# MCH_FPGA_Power.net
KiCad netlist of a schematic drawn in Altium Designer
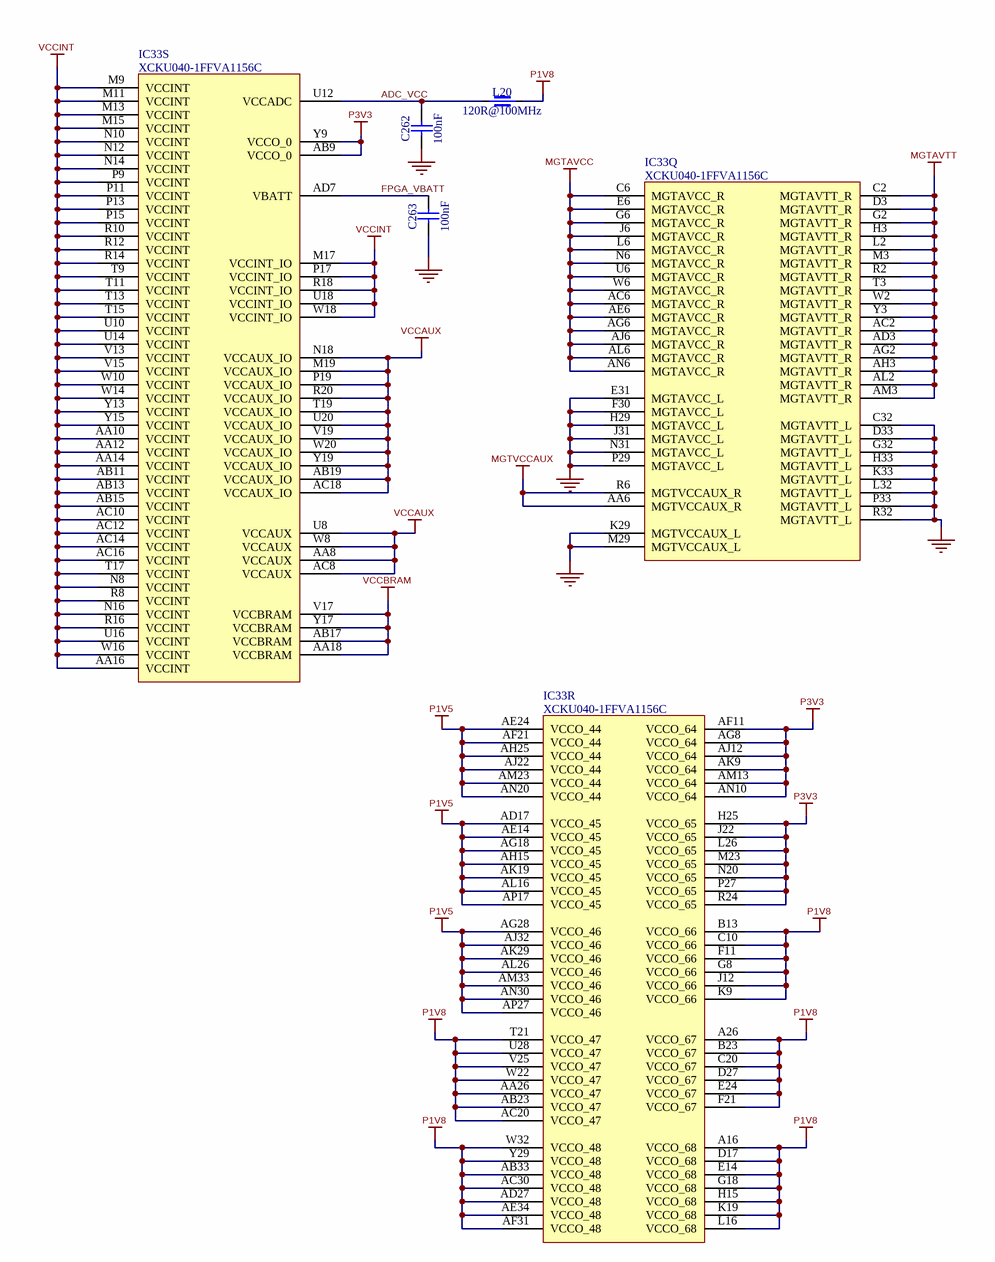
[diagram p0: MCH_FPGA_Power.SchDoc]

(export (version "E")
  (design (tool "Eeschema 10.0.6"))
  (components
    (comp (ref "C262")
      (value "100nF")
      (footprint "CAPC0603X33N")
      (description "Non-polarised capacitor")
      (fields
        (field (name "MANUFACTURER PART NUMBER") "CC0201_100NF_6.3V_10%_X5R")
        (field (name "MANUFACTURER") "GENERIC")
        (field (name "AUTHOR") "CERN DEM JLC")
      )
      (libsource (lib "Capacitors") (part "Capacitor - non polarized"))
    )
    (comp (ref "C263")
      (value "100nF")
      (footprint "CAPC0603X33N")
      (description "Non-polarised capacitor")
      (fields
        (field (name "MANUFACTURER PART NUMBER") "CC0201_100NF_6.3V_10%_X5R")
        (field (name "MANUFACTURER") "GENERIC")
        (field (name "AUTHOR") "CERN DEM JLC")
      )
      (libsource (lib "Capacitors") (part "Capacitor - non polarized"))
    )
    (comp (ref "IC33")
      (value "XCKU040-1FFVA1156C")
      (footprint "BGA1156C100P34X34_3500X3500X350")
      (description "Kintex UltraScale FPGA, 520 I/O, 530K Cells, 1156-Ball BGA, Speed Grade 1, Commercial Grade")
      (fields (field (name "MANUFACTURER") "XILINX") (field (name "AUTHOR") "CERN DEM CA"))
      (libsource (lib "ICs And Semiconductors") (part "XCKU040-1FFVA1156C"))
    )
    (comp (ref "L20")
      (value "120R@100MHz")
      (footprint "INDC1005X55N")
      (fields
        (field (name "MANUFACTURER PART NUMBER") "BLM15PX121SN1D")
        (field (name "MANUFACTURER") "MURATA")
        (field (name "PART NUMBER") "IND0402_MURATA_BLM15PX121SN1D")
        (field (name "AUTHOR") "CERN DEM JMW")
      )
      (libsource (lib "Inductors & Transformers") (part "Ferrite Bead"))
    )
  )
  (nets
    (net (code "1") (name "/ADC_VCC") (class "Default")
      (node (ref "C262") (pin "2") (pinfunction "2_2") (pintype "passive"))
      (node (ref "IC33") (pin "U12") (pinfunction "VCCADC_U12") (pintype "power_in"))
      (node (ref "L20") (pin "1") (pinfunction "1_1") (pintype "passive"))
    )
    (net (code "2") (name "/FPGA_VBATT") (class "Default")
      (node (ref "C263") (pin "2") (pinfunction "2_2") (pintype "passive"))
      (node (ref "IC33") (pin "AD7") (pinfunction "VBATT_AD7") (pintype "power_in"))
    )
    (net (code "3") (name "GND") (class "Default")
      (node (ref "C262") (pin "1") (pinfunction "1_1") (pintype "passive"))
      (node (ref "C263") (pin "1") (pinfunction "1_1") (pintype "passive"))
      (node (ref "IC33") (pin "C32") (pinfunction "MGTAVTT_L_C32") (pintype "power_in"))
      (node (ref "IC33") (pin "D33") (pinfunction "MGTAVTT_L_D33") (pintype "power_in"))
      (node (ref "IC33") (pin "E31") (pinfunction "MGTAVCC_L_E31") (pintype "power_in"))
      (node (ref "IC33") (pin "F30") (pinfunction "MGTAVCC_L_F30") (pintype "power_in"))
      (node (ref "IC33") (pin "G32") (pinfunction "MGTAVTT_L_G32") (pintype "power_in"))
      (node (ref "IC33") (pin "H29") (pinfunction "MGTAVCC_L_H29") (pintype "power_in"))
      (node (ref "IC33") (pin "H33") (pinfunction "MGTAVTT_L_H33") (pintype "power_in"))
      (node (ref "IC33") (pin "J31") (pinfunction "MGTAVCC_L_J31") (pintype "power_in"))
      (node (ref "IC33") (pin "K29") (pinfunction "MGTVCCAUX_L_K29") (pintype "power_in"))
      (node (ref "IC33") (pin "K33") (pinfunction "MGTAVTT_L_K33") (pintype "power_in"))
      (node (ref "IC33") (pin "L32") (pinfunction "MGTAVTT_L_L32") (pintype "power_in"))
      (node (ref "IC33") (pin "M29") (pinfunction "MGTVCCAUX_L_M29") (pintype "power_in"))
      (node (ref "IC33") (pin "N31") (pinfunction "MGTAVCC_L_N31") (pintype "power_in"))
      (node (ref "IC33") (pin "P29") (pinfunction "MGTAVCC_L_P29") (pintype "power_in"))
      (node (ref "IC33") (pin "P33") (pinfunction "MGTAVTT_L_P33") (pintype "power_in"))
      (node (ref "IC33") (pin "R32") (pinfunction "MGTAVTT_L_R32") (pintype "power_in"))
    )
    (net (code "4") (name "MGTAVCC") (class "Default")
      (node (ref "IC33") (pin "AC6") (pinfunction "MGTAVCC_R_AC6") (pintype "power_in"))
      (node (ref "IC33") (pin "AE6") (pinfunction "MGTAVCC_R_AE6") (pintype "power_in"))
      (node (ref "IC33") (pin "AG6") (pinfunction "MGTAVCC_R_AG6") (pintype "power_in"))
      (node (ref "IC33") (pin "AJ6") (pinfunction "MGTAVCC_R_AJ6") (pintype "power_in"))
      (node (ref "IC33") (pin "AL6") (pinfunction "MGTAVCC_R_AL6") (pintype "power_in"))
      (node (ref "IC33") (pin "AN6") (pinfunction "MGTAVCC_R_AN6") (pintype "power_in"))
      (node (ref "IC33") (pin "C6") (pinfunction "MGTAVCC_R_C6") (pintype "power_in"))
      (node (ref "IC33") (pin "E6") (pinfunction "MGTAVCC_R_E6") (pintype "power_in"))
      (node (ref "IC33") (pin "G6") (pinfunction "MGTAVCC_R_G6") (pintype "power_in"))
      (node (ref "IC33") (pin "J6") (pinfunction "MGTAVCC_R_J6") (pintype "power_in"))
      (node (ref "IC33") (pin "L6") (pinfunction "MGTAVCC_R_L6") (pintype "power_in"))
      (node (ref "IC33") (pin "N6") (pinfunction "MGTAVCC_R_N6") (pintype "power_in"))
      (node (ref "IC33") (pin "U6") (pinfunction "MGTAVCC_R_U6") (pintype "power_in"))
      (node (ref "IC33") (pin "W6") (pinfunction "MGTAVCC_R_W6") (pintype "power_in"))
    )
    (net (code "5") (name "MGTAVTT") (class "Default")
      (node (ref "IC33") (pin "AC2") (pinfunction "MGTAVTT_R_AC2") (pintype "power_in"))
      (node (ref "IC33") (pin "AD3") (pinfunction "MGTAVTT_R_AD3") (pintype "power_in"))
      (node (ref "IC33") (pin "AG2") (pinfunction "MGTAVTT_R_AG2") (pintype "power_in"))
      (node (ref "IC33") (pin "AH3") (pinfunction "MGTAVTT_R_AH3") (pintype "power_in"))
      (node (ref "IC33") (pin "AL2") (pinfunction "MGTAVTT_R_AL2") (pintype "power_in"))
      (node (ref "IC33") (pin "AM3") (pinfunction "MGTAVTT_R_AM3") (pintype "power_in"))
      (node (ref "IC33") (pin "C2") (pinfunction "MGTAVTT_R_C2") (pintype "power_in"))
      (node (ref "IC33") (pin "D3") (pinfunction "MGTAVTT_R_D3") (pintype "power_in"))
      (node (ref "IC33") (pin "G2") (pinfunction "MGTAVTT_R_G2") (pintype "power_in"))
      (node (ref "IC33") (pin "H3") (pinfunction "MGTAVTT_R_H3") (pintype "power_in"))
      (node (ref "IC33") (pin "L2") (pinfunction "MGTAVTT_R_L2") (pintype "power_in"))
      (node (ref "IC33") (pin "M3") (pinfunction "MGTAVTT_R_M3") (pintype "power_in"))
      (node (ref "IC33") (pin "R2") (pinfunction "MGTAVTT_R_R2") (pintype "power_in"))
      (node (ref "IC33") (pin "T3") (pinfunction "MGTAVTT_R_T3") (pintype "power_in"))
      (node (ref "IC33") (pin "W2") (pinfunction "MGTAVTT_R_W2") (pintype "power_in"))
      (node (ref "IC33") (pin "Y3") (pinfunction "MGTAVTT_R_Y3") (pintype "power_in"))
    )
    (net (code "6") (name "MGTVCCAUX") (class "Default")
      (node (ref "IC33") (pin "AA6") (pinfunction "MGTVCCAUX_R_AA6") (pintype "power_in"))
      (node (ref "IC33") (pin "R6") (pinfunction "MGTVCCAUX_R_R6") (pintype "power_in"))
    )
    (net (code "7") (name "P1V5") (class "Default")
      (node (ref "IC33") (pin "AD17") (pinfunction "VCCO_45_AD17") (pintype "power_in"))
      (node (ref "IC33") (pin "AE14") (pinfunction "VCCO_45_AE14") (pintype "power_in"))
      (node (ref "IC33") (pin "AE24") (pinfunction "VCCO_44_AE24") (pintype "power_in"))
      (node (ref "IC33") (pin "AF21") (pinfunction "VCCO_44_AF21") (pintype "power_in"))
      (node (ref "IC33") (pin "AG18") (pinfunction "VCCO_45_AG18") (pintype "power_in"))
      (node (ref "IC33") (pin "AG28") (pinfunction "VCCO_46_AG28") (pintype "power_in"))
      (node (ref "IC33") (pin "AH15") (pinfunction "VCCO_45_AH15") (pintype "power_in"))
      (node (ref "IC33") (pin "AH25") (pinfunction "VCCO_44_AH25") (pintype "power_in"))
      (node (ref "IC33") (pin "AJ22") (pinfunction "VCCO_44_AJ22") (pintype "power_in"))
      (node (ref "IC33") (pin "AJ32") (pinfunction "VCCO_46_AJ32") (pintype "power_in"))
      (node (ref "IC33") (pin "AK19") (pinfunction "VCCO_45_AK19") (pintype "power_in"))
      (node (ref "IC33") (pin "AK29") (pinfunction "VCCO_46_AK29") (pintype "power_in"))
      (node (ref "IC33") (pin "AL16") (pinfunction "VCCO_45_AL16") (pintype "power_in"))
      (node (ref "IC33") (pin "AL26") (pinfunction "VCCO_46_AL26") (pintype "power_in"))
      (node (ref "IC33") (pin "AM23") (pinfunction "VCCO_44_AM23") (pintype "power_in"))
      (node (ref "IC33") (pin "AM33") (pinfunction "VCCO_46_AM33") (pintype "power_in"))
      (node (ref "IC33") (pin "AN20") (pinfunction "VCCO_44_AN20") (pintype "power_in"))
      (node (ref "IC33") (pin "AN30") (pinfunction "VCCO_46_AN30") (pintype "power_in"))
      (node (ref "IC33") (pin "AP17") (pinfunction "VCCO_45_AP17") (pintype "power_in"))
      (node (ref "IC33") (pin "AP27") (pinfunction "VCCO_46_AP27") (pintype "power_in"))
    )
    (net (code "8") (name "P1V8") (class "Default")
      (node (ref "IC33") (pin "A16") (pinfunction "VCCO_68_A16") (pintype "power_in"))
      (node (ref "IC33") (pin "A26") (pinfunction "VCCO_67_A26") (pintype "power_in"))
      (node (ref "IC33") (pin "AA26") (pinfunction "VCCO_47_AA26") (pintype "power_in"))
      (node (ref "IC33") (pin "AB23") (pinfunction "VCCO_47_AB23") (pintype "power_in"))
      (node (ref "IC33") (pin "AB33") (pinfunction "VCCO_48_AB33") (pintype "power_in"))
      (node (ref "IC33") (pin "AC20") (pinfunction "VCCO_47_AC20") (pintype "power_in"))
      (node (ref "IC33") (pin "AC30") (pinfunction "VCCO_48_AC30") (pintype "power_in"))
      (node (ref "IC33") (pin "AD27") (pinfunction "VCCO_48_AD27") (pintype "power_in"))
      (node (ref "IC33") (pin "AE34") (pinfunction "VCCO_48_AE34") (pintype "power_in"))
      (node (ref "IC33") (pin "AF31") (pinfunction "VCCO_48_AF31") (pintype "power_in"))
      (node (ref "IC33") (pin "B13") (pinfunction "VCCO_66_B13") (pintype "power_in"))
      (node (ref "IC33") (pin "B23") (pinfunction "VCCO_67_B23") (pintype "power_in"))
      (node (ref "IC33") (pin "C10") (pinfunction "VCCO_66_C10") (pintype "power_in"))
      (node (ref "IC33") (pin "C20") (pinfunction "VCCO_67_C20") (pintype "power_in"))
      (node (ref "IC33") (pin "D17") (pinfunction "VCCO_68_D17") (pintype "power_in"))
      (node (ref "IC33") (pin "D27") (pinfunction "VCCO_67_D27") (pintype "power_in"))
      (node (ref "IC33") (pin "E14") (pinfunction "VCCO_68_E14") (pintype "power_in"))
      (node (ref "IC33") (pin "E24") (pinfunction "VCCO_67_E24") (pintype "power_in"))
      (node (ref "IC33") (pin "F11") (pinfunction "VCCO_66_F11") (pintype "power_in"))
      (node (ref "IC33") (pin "F21") (pinfunction "VCCO_67_F21") (pintype "power_in"))
      (node (ref "IC33") (pin "G18") (pinfunction "VCCO_68_G18") (pintype "power_in"))
      (node (ref "IC33") (pin "G8") (pinfunction "VCCO_66_G8") (pintype "power_in"))
      (node (ref "IC33") (pin "H15") (pinfunction "VCCO_68_H15") (pintype "power_in"))
      (node (ref "IC33") (pin "J12") (pinfunction "VCCO_66_J12") (pintype "power_in"))
      (node (ref "IC33") (pin "K19") (pinfunction "VCCO_68_K19") (pintype "power_in"))
      (node (ref "IC33") (pin "K9") (pinfunction "VCCO_66_K9") (pintype "power_in"))
      (node (ref "IC33") (pin "L16") (pinfunction "VCCO_68_L16") (pintype "power_in"))
      (node (ref "IC33") (pin "T21") (pinfunction "VCCO_47_T21") (pintype "power_in"))
      (node (ref "IC33") (pin "U28") (pinfunction "VCCO_47_U28") (pintype "power_in"))
      (node (ref "IC33") (pin "V25") (pinfunction "VCCO_47_V25") (pintype "power_in"))
      (node (ref "IC33") (pin "W22") (pinfunction "VCCO_47_W22") (pintype "power_in"))
      (node (ref "IC33") (pin "W32") (pinfunction "VCCO_48_W32") (pintype "power_in"))
      (node (ref "IC33") (pin "Y29") (pinfunction "VCCO_48_Y29") (pintype "power_in"))
      (node (ref "L20") (pin "2") (pinfunction "2_2") (pintype "passive"))
    )
    (net (code "9") (name "P3V3") (class "Default")
      (node (ref "IC33") (pin "AB9") (pinfunction "VCCO_0_AB9") (pintype "power_in"))
      (node (ref "IC33") (pin "AF11") (pinfunction "VCCO_64_AF11") (pintype "power_in"))
      (node (ref "IC33") (pin "AG8") (pinfunction "VCCO_64_AG8") (pintype "power_in"))
      (node (ref "IC33") (pin "AJ12") (pinfunction "VCCO_64_AJ12") (pintype "power_in"))
      (node (ref "IC33") (pin "AK9") (pinfunction "VCCO_64_AK9") (pintype "power_in"))
      (node (ref "IC33") (pin "AM13") (pinfunction "VCCO_64_AM13") (pintype "power_in"))
      (node (ref "IC33") (pin "AN10") (pinfunction "VCCO_64_AN10") (pintype "power_in"))
      (node (ref "IC33") (pin "H25") (pinfunction "VCCO_65_H25") (pintype "power_in"))
      (node (ref "IC33") (pin "J22") (pinfunction "VCCO_65_J22") (pintype "power_in"))
      (node (ref "IC33") (pin "L26") (pinfunction "VCCO_65_L26") (pintype "power_in"))
      (node (ref "IC33") (pin "M23") (pinfunction "VCCO_65_M23") (pintype "power_in"))
      (node (ref "IC33") (pin "N20") (pinfunction "VCCO_65_N20") (pintype "power_in"))
      (node (ref "IC33") (pin "P27") (pinfunction "VCCO_65_P27") (pintype "power_in"))
      (node (ref "IC33") (pin "R24") (pinfunction "VCCO_65_R24") (pintype "power_in"))
      (node (ref "IC33") (pin "Y9") (pinfunction "VCCO_0_Y9") (pintype "power_in"))
    )
    (net (code "10") (name "VCCAUX") (class "Default")
      (node (ref "IC33") (pin "AA8") (pinfunction "VCCAUX_AA8") (pintype "power_in"))
      (node (ref "IC33") (pin "AB19") (pinfunction "VCCAUX_IO_AB19") (pintype "power_in"))
      (node (ref "IC33") (pin "AC18") (pinfunction "VCCAUX_IO_AC18") (pintype "power_in"))
      (node (ref "IC33") (pin "AC8") (pinfunction "VCCAUX_AC8") (pintype "power_in"))
      (node (ref "IC33") (pin "M19") (pinfunction "VCCAUX_IO_M19") (pintype "power_in"))
      (node (ref "IC33") (pin "N18") (pinfunction "VCCAUX_IO_N18") (pintype "power_in"))
      (node (ref "IC33") (pin "P19") (pinfunction "VCCAUX_IO_P19") (pintype "power_in"))
      (node (ref "IC33") (pin "R20") (pinfunction "VCCAUX_IO_R20") (pintype "power_in"))
      (node (ref "IC33") (pin "T19") (pinfunction "VCCAUX_IO_T19") (pintype "power_in"))
      (node (ref "IC33") (pin "U20") (pinfunction "VCCAUX_IO_U20") (pintype "power_in"))
      (node (ref "IC33") (pin "U8") (pinfunction "VCCAUX_U8") (pintype "power_in"))
      (node (ref "IC33") (pin "V19") (pinfunction "VCCAUX_IO_V19") (pintype "power_in"))
      (node (ref "IC33") (pin "W20") (pinfunction "VCCAUX_IO_W20") (pintype "power_in"))
      (node (ref "IC33") (pin "W8") (pinfunction "VCCAUX_W8") (pintype "power_in"))
      (node (ref "IC33") (pin "Y19") (pinfunction "VCCAUX_IO_Y19") (pintype "power_in"))
    )
    (net (code "11") (name "VCCBRAM") (class "Default")
      (node (ref "IC33") (pin "AA18") (pinfunction "VCCBRAM_AA18") (pintype "power_in"))
      (node (ref "IC33") (pin "AB17") (pinfunction "VCCBRAM_AB17") (pintype "power_in"))
      (node (ref "IC33") (pin "V17") (pinfunction "VCCBRAM_V17") (pintype "power_in"))
      (node (ref "IC33") (pin "Y17") (pinfunction "VCCBRAM_Y17") (pintype "power_in"))
    )
    (net (code "12") (name "VCCINT") (class "Default")
      (node (ref "IC33") (pin "AA10") (pinfunction "VCCINT_AA10") (pintype "power_in"))
      (node (ref "IC33") (pin "AA12") (pinfunction "VCCINT_AA12") (pintype "power_in"))
      (node (ref "IC33") (pin "AA14") (pinfunction "VCCINT_AA14") (pintype "power_in"))
      (node (ref "IC33") (pin "AA16") (pinfunction "VCCINT_AA16") (pintype "power_in"))
      (node (ref "IC33") (pin "AB11") (pinfunction "VCCINT_AB11") (pintype "power_in"))
      (node (ref "IC33") (pin "AB13") (pinfunction "VCCINT_AB13") (pintype "power_in"))
      (node (ref "IC33") (pin "AB15") (pinfunction "VCCINT_AB15") (pintype "power_in"))
      (node (ref "IC33") (pin "AC10") (pinfunction "VCCINT_AC10") (pintype "power_in"))
      (node (ref "IC33") (pin "AC12") (pinfunction "VCCINT_AC12") (pintype "power_in"))
      (node (ref "IC33") (pin "AC14") (pinfunction "VCCINT_AC14") (pintype "power_in"))
      (node (ref "IC33") (pin "AC16") (pinfunction "VCCINT_AC16") (pintype "power_in"))
      (node (ref "IC33") (pin "M11") (pinfunction "VCCINT_M11") (pintype "power_in"))
      (node (ref "IC33") (pin "M13") (pinfunction "VCCINT_M13") (pintype "power_in"))
      (node (ref "IC33") (pin "M15") (pinfunction "VCCINT_M15") (pintype "power_in"))
      (node (ref "IC33") (pin "M17") (pinfunction "VCCINT_IO_M17") (pintype "power_in"))
      (node (ref "IC33") (pin "M9") (pinfunction "VCCINT_M9") (pintype "power_in"))
      (node (ref "IC33") (pin "N10") (pinfunction "VCCINT_N10") (pintype "power_in"))
      (node (ref "IC33") (pin "N12") (pinfunction "VCCINT_N12") (pintype "power_in"))
      (node (ref "IC33") (pin "N14") (pinfunction "VCCINT_N14") (pintype "power_in"))
      (node (ref "IC33") (pin "N16") (pinfunction "VCCINT_N16") (pintype "power_in"))
      (node (ref "IC33") (pin "N8") (pinfunction "VCCINT_N8") (pintype "power_in"))
      (node (ref "IC33") (pin "P11") (pinfunction "VCCINT_P11") (pintype "power_in"))
      (node (ref "IC33") (pin "P13") (pinfunction "VCCINT_P13") (pintype "power_in"))
      (node (ref "IC33") (pin "P15") (pinfunction "VCCINT_P15") (pintype "power_in"))
      (node (ref "IC33") (pin "P17") (pinfunction "VCCINT_IO_P17") (pintype "power_in"))
      (node (ref "IC33") (pin "P9") (pinfunction "VCCINT_P9") (pintype "power_in"))
      (node (ref "IC33") (pin "R10") (pinfunction "VCCINT_R10") (pintype "power_in"))
      (node (ref "IC33") (pin "R12") (pinfunction "VCCINT_R12") (pintype "power_in"))
      (node (ref "IC33") (pin "R14") (pinfunction "VCCINT_R14") (pintype "power_in"))
      (node (ref "IC33") (pin "R16") (pinfunction "VCCINT_R16") (pintype "power_in"))
      (node (ref "IC33") (pin "R18") (pinfunction "VCCINT_IO_R18") (pintype "power_in"))
      (node (ref "IC33") (pin "R8") (pinfunction "VCCINT_R8") (pintype "power_in"))
      (node (ref "IC33") (pin "T11") (pinfunction "VCCINT_T11") (pintype "power_in"))
      (node (ref "IC33") (pin "T13") (pinfunction "VCCINT_T13") (pintype "power_in"))
      (node (ref "IC33") (pin "T15") (pinfunction "VCCINT_T15") (pintype "power_in"))
      (node (ref "IC33") (pin "T17") (pinfunction "VCCINT_T17") (pintype "power_in"))
      (node (ref "IC33") (pin "T9") (pinfunction "VCCINT_T9") (pintype "power_in"))
      (node (ref "IC33") (pin "U10") (pinfunction "VCCINT_U10") (pintype "power_in"))
      (node (ref "IC33") (pin "U14") (pinfunction "VCCINT_U14") (pintype "power_in"))
      (node (ref "IC33") (pin "U16") (pinfunction "VCCINT_U16") (pintype "power_in"))
      (node (ref "IC33") (pin "U18") (pinfunction "VCCINT_IO_U18") (pintype "power_in"))
      (node (ref "IC33") (pin "V13") (pinfunction "VCCINT_V13") (pintype "power_in"))
      (node (ref "IC33") (pin "V15") (pinfunction "VCCINT_V15") (pintype "power_in"))
      (node (ref "IC33") (pin "W10") (pinfunction "VCCINT_W10") (pintype "power_in"))
      (node (ref "IC33") (pin "W14") (pinfunction "VCCINT_W14") (pintype "power_in"))
      (node (ref "IC33") (pin "W16") (pinfunction "VCCINT_W16") (pintype "power_in"))
      (node (ref "IC33") (pin "W18") (pinfunction "VCCINT_IO_W18") (pintype "power_in"))
      (node (ref "IC33") (pin "Y13") (pinfunction "VCCINT_Y13") (pintype "power_in"))
      (node (ref "IC33") (pin "Y15") (pinfunction "VCCINT_Y15") (pintype "power_in"))
    )
  )
)
